# Micron-6.net
KiCad netlist of a schematic drawn in Altium Designer
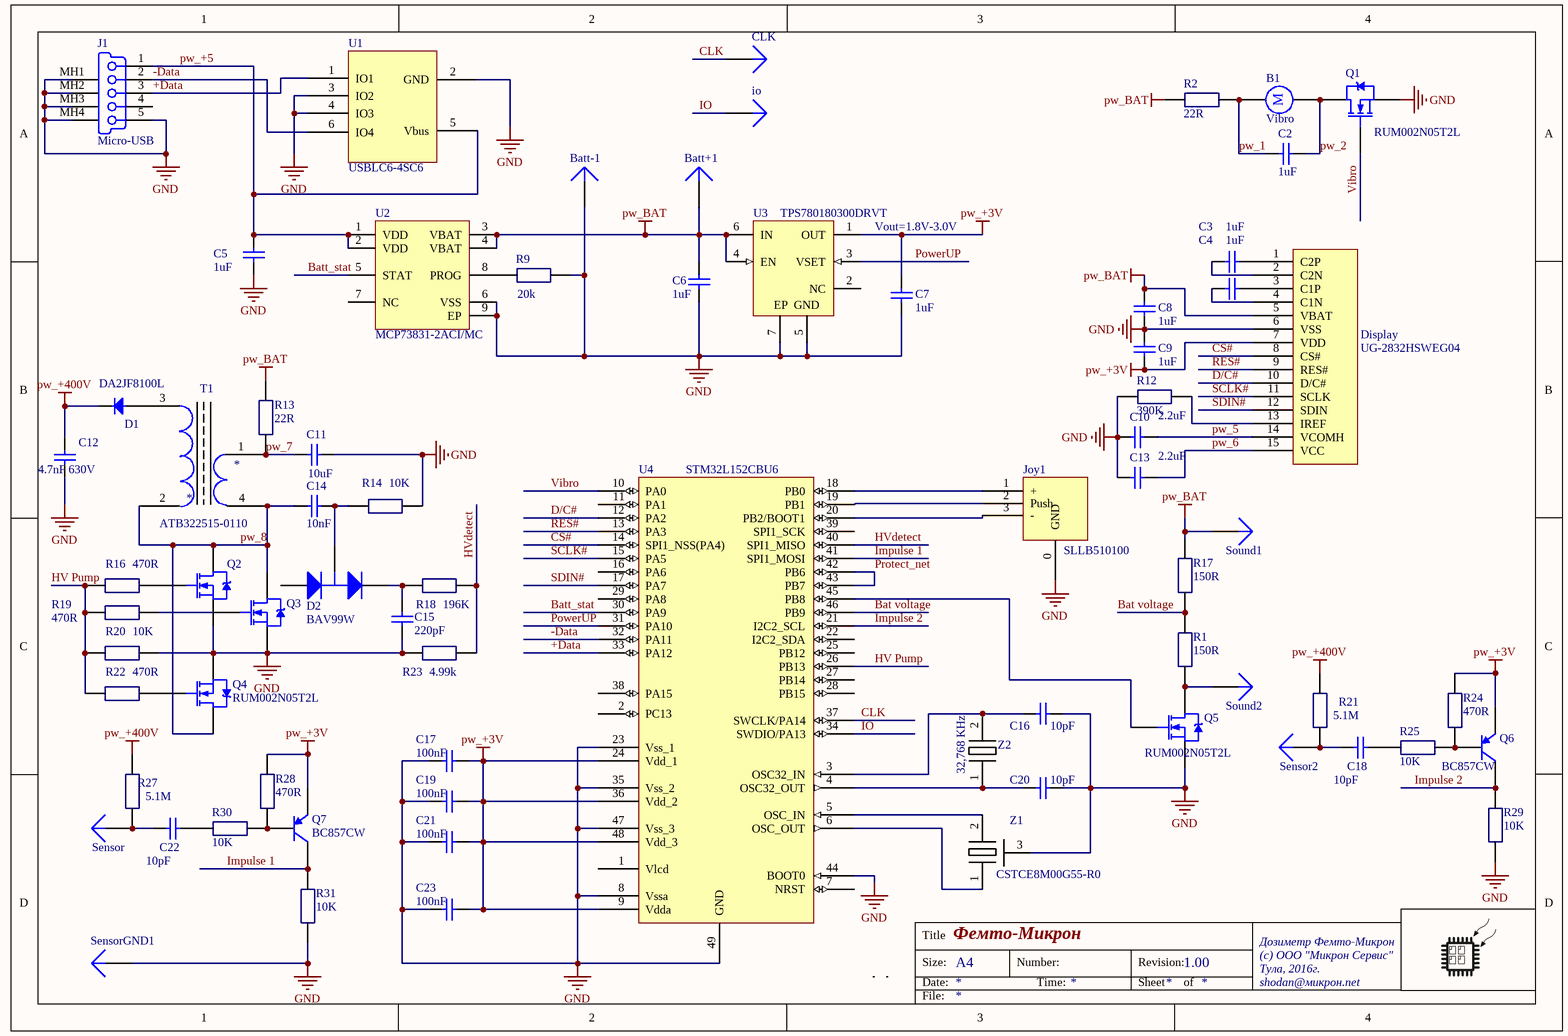
[diagram p0: Micron-6.SchDoc]

(export (version "E")
  (design (tool "Eeschema 10.0.6"))
  (components
    (comp (ref "B1")
      (value "Vibro")
      (footprint "Vibro 4hobby")
      (description "Motor, General Kind")
      (fields (field (name "PUBLISHER") "Altium Limited"))
      (libsource (lib "Miscellaneous Devices") (part "Motor"))
    )
    (comp (ref "Batt+1")
      (value "~")
      (footprint "Sensor contact")
      (description "Plug")
      (fields (field (name "PUBLISHER") "Altium Limited"))
      (libsource (lib "Miscellaneous Connectors") (part "Plug"))
    )
    (comp (ref "Batt-1")
      (value "~")
      (footprint "Sensor contact")
      (description "Plug")
      (fields (field (name "PUBLISHER") "Altium Limited"))
      (libsource (lib "Miscellaneous Connectors") (part "Plug"))
    )
    (comp (ref "C2")
      (value "1uF")
      (footprint "0402 AVX CHK2")
      (description "Capacitor (Semiconductor SIM Model)")
      (fields (field (name "PUBLISHER") "Altium Limited"))
      (libsource (lib "My SCH library") (part "CAPACITOR"))
    )
    (comp (ref "C3")
      (value "1uF")
      (footprint "0402 AVX CHK2")
      (description "Capacitor (Semiconductor SIM Model)")
      (fields (field (name "PUBLISHER") "Altium Limited"))
      (libsource (lib "My SCH library") (part "CAPACITOR"))
    )
    (comp (ref "C4")
      (value "1uF")
      (footprint "0402 AVX CHK2")
      (description "Capacitor (Semiconductor SIM Model)")
      (fields (field (name "PUBLISHER") "Altium Limited"))
      (libsource (lib "My SCH library") (part "CAPACITOR"))
    )
    (comp (ref "C5")
      (value "1uF")
      (footprint "0402 AVX CHK2")
      (description "Capacitor (Semiconductor SIM Model)")
      (fields (field (name "PUBLISHER") "Altium Limited"))
      (libsource (lib "Miscellaneous Devices") (part "Cap Semi"))
    )
    (comp (ref "C6")
      (value "1uF")
      (footprint "0402 AVX CHK2")
      (description "Capacitor (Semiconductor SIM Model)")
      (fields (field (name "PUBLISHER") "Altium Limited"))
      (libsource (lib "My SCH library") (part "CAPACITOR"))
    )
    (comp (ref "C7")
      (value "1uF")
      (footprint "0402 AVX CHK2")
      (description "Capacitor (Semiconductor SIM Model)")
      (fields (field (name "PUBLISHER") "Altium Limited"))
      (libsource (lib "My SCH library") (part "CAPACITOR"))
    )
    (comp (ref "C8")
      (value "1uF")
      (footprint "0402 AVX CHK2")
      (description "Capacitor (Semiconductor SIM Model)")
      (fields (field (name "PUBLISHER") "Altium Limited"))
      (libsource (lib "My SCH library") (part "CAPACITOR"))
    )
    (comp (ref "C9")
      (value "1uF")
      (footprint "0402 AVX CHK2")
      (description "Capacitor (Semiconductor SIM Model)")
      (fields (field (name "PUBLISHER") "Altium Limited"))
      (libsource (lib "My SCH library") (part "CAPACITOR"))
    )
    (comp (ref "C10")
      (value "2.2uF")
      (footprint "Yegeo 0603")
      (description "Capacitor (Semiconductor SIM Model)")
      (fields (field (name "PUBLISHER") "Altium Limited"))
      (libsource (lib "My SCH library") (part "CAPACITOR"))
    )
    (comp (ref "C11")
      (value "10uF")
      (footprint "1608[0603]")
      (description "Capacitor (Semiconductor SIM Model)")
      (fields (field (name "PUBLISHER") "Altium Limited"))
      (libsource (lib "Miscellaneous Devices") (part "Cap Semi"))
    )
    (comp (ref "C12")
      (value "4.7nF 630V")
      (footprint "Miscellaneous Devices:C1206")
      (description "Capacitor (Semiconductor SIM Model)")
      (fields (field (name "PUBLISHER") "Altium Limited"))
      (libsource (lib "Miscellaneous Devices") (part "Cap Semi"))
    )
    (comp (ref "C13")
      (value "2.2uF")
      (footprint "Yegeo 0603")
      (description "Capacitor (Semiconductor SIM Model)")
      (fields (field (name "PUBLISHER") "Altium Limited"))
      (libsource (lib "My SCH library") (part "CAPACITOR"))
    )
    (comp (ref "C14")
      (value "10nF")
      (footprint "0402 AVX CHK2")
      (description "Capacitor (Semiconductor SIM Model)")
      (libsource (lib "Miscellaneous Devices") (part "Cap Semi"))
    )
    (comp (ref "C15")
      (value "220pF")
      (footprint "0402 AVX CHK2")
      (description "Capacitor (Semiconductor SIM Model)")
      (libsource (lib "Miscellaneous Devices") (part "Cap Semi"))
    )
    (comp (ref "C16")
      (value "10pF")
      (footprint "0402 AVX CHK2")
      (description "Capacitor (Semiconductor SIM Model)")
      (fields (field (name "PUBLISHER") "Altium Limited"))
      (libsource (lib "Miscellaneous Devices") (part "Cap Semi"))
    )
    (comp (ref "C17")
      (value "100nF")
      (footprint "0402 AVX CHK2")
      (description "Capacitor (Semiconductor SIM Model)")
      (fields (field (name "PUBLISHER") "Altium Limited"))
      (libsource (lib "Miscellaneous Devices") (part "Cap Semi"))
    )
    (comp (ref "C18")
      (value "10pF")
      (footprint "CC1206JRNPOBBN100")
      (description "Capacitor (Semiconductor SIM Model)")
      (fields (field (name "PUBLISHER") "Altium Limited"))
      (libsource (lib "Miscellaneous Devices") (part "Cap Semi"))
    )
    (comp (ref "C19")
      (value "100nF")
      (footprint "0402 AVX CHK2")
      (description "Capacitor (Semiconductor SIM Model)")
      (fields (field (name "PUBLISHER") "Altium Limited"))
      (libsource (lib "Miscellaneous Devices") (part "Cap Semi"))
    )
    (comp (ref "C20")
      (value "10pF")
      (footprint "0402 AVX CHK2")
      (description "Capacitor (Semiconductor SIM Model)")
      (fields (field (name "PUBLISHER") "Altium Limited"))
      (libsource (lib "Miscellaneous Devices") (part "Cap Semi"))
    )
    (comp (ref "C21")
      (value "100nF")
      (footprint "0402 AVX CHK2")
      (description "Capacitor (Semiconductor SIM Model)")
      (fields (field (name "PUBLISHER") "Altium Limited"))
      (libsource (lib "Miscellaneous Devices") (part "Cap Semi"))
    )
    (comp (ref "C22")
      (value "10pF")
      (footprint "CC1206JRNPOBBN100")
      (description "Capacitor (Semiconductor SIM Model)")
      (fields (field (name "PUBLISHER") "Altium Limited"))
      (libsource (lib "Miscellaneous Devices") (part "Cap Semi"))
    )
    (comp (ref "C23")
      (value "100nF")
      (footprint "0402 AVX CHK2")
      (description "Capacitor (Semiconductor SIM Model)")
      (fields (field (name "PUBLISHER") "Altium Limited"))
      (libsource (lib "Miscellaneous Devices") (part "Cap Semi"))
    )
    (comp (ref "CLK")
      (value "~")
      (footprint "Sensor contact")
      (description "Plug")
      (fields (field (name "PUBLISHER") "Altium Limited"))
      (libsource (lib "Miscellaneous Connectors") (part "Plug"))
    )
    (comp (ref "D1")
      (value "DA2JF8100L")
      (footprint "DA2JF8100L(chk)")
      (description "Diode")
      (libsource (lib "Diodes") (part "Diode"))
    )
    (comp (ref "D2")
      (value "BAV99W")
      (footprint "BAV99W")
      (description "Silicon Switching Diode Array for High-Speed Switching")
      (fields (field (name "PUBLISHER") "Altium Limited"))
      (libsource (lib "Infineon Discrete Diode") (part "BAV99"))
    )
    (comp (ref "Display")
      (value "UG-2832HSWEG04")
      (footprint "UG-2832HSWEG04 - duplicate")
      (libsource (lib "My SCH library") (part "UG-2832HSWEG04"))
    )
    (comp (ref "io")
      (value "~")
      (footprint "Sensor contact")
      (description "Plug")
      (fields (field (name "PUBLISHER") "Altium Limited"))
      (libsource (lib "Miscellaneous Connectors") (part "Plug"))
    )
    (comp (ref "J1")
      (value "Micro-USB")
      (footprint "10118193-0001LF")
      (libsource (lib "Molex Serial Bus Mini USB") (part "0481900001"))
    )
    (comp (ref "Joy1")
      (value "SLLB510100")
      (footprint "SLLB510100")
      (libsource (lib "My SCH library") (part "Joystik"))
    )
    (comp (ref "Q1")
      (value "RUM002N05T2L")
      (footprint "RUM002N05")
      (description "HEXFET Power MOSFET")
      (fields (field (name "PUBLISHER") "Altium Limited"))
      (libsource (lib "IR Discrete MOSFET - Power") (part "IRLML2402"))
    )
    (comp (ref "Q2")
      (value "RUM002N05T2L")
      (footprint "RUM002N05")
      (description "HEXFET Power MOSFET")
      (fields (field (name "PUBLISHER") "Altium Limited"))
      (libsource (lib "IR Discrete MOSFET - Power") (part "IRLML2402"))
    )
    (comp (ref "Q3")
      (value "RUM002N05T2L")
      (footprint "RUM002N05")
      (description "HEXFET Power MOSFET")
      (fields (field (name "PUBLISHER") "Altium Limited"))
      (libsource (lib "IR Discrete MOSFET - Power") (part "IRLML2402"))
    )
    (comp (ref "Q4")
      (value "RUM002N05T2L")
      (footprint "RUM002N05")
      (description "HEXFET Power MOSFET")
      (fields (field (name "PUBLISHER") "Altium Limited"))
      (libsource (lib "IR Discrete MOSFET - Power") (part "IRLML2402"))
    )
    (comp (ref "Q5")
      (value "RUM002N05T2L")
      (footprint "RUM002N05")
      (description "HEXFET Power MOSFET")
      (fields (field (name "PUBLISHER") "Altium Limited"))
      (libsource (lib "IR Discrete MOSFET - Power") (part "IRLML2402"))
    )
    (comp (ref "Q6")
      (value "BC857CW")
      (footprint "SOT323_L2")
      (description "PNP General-purpose Transistor")
      (fields (field (name "PUBLISHER") "Altium Limited"))
      (libsource (lib "Philips Discrete BJT - Low Power") (part "BC857CW"))
    )
    (comp (ref "Q7")
      (value "BC857CW")
      (footprint "SOT323_L2")
      (description "PNP General-purpose Transistor")
      (fields (field (name "PUBLISHER") "Altium Limited"))
      (libsource (lib "Philips Discrete BJT - Low Power") (part "BC857CW"))
    )
    (comp (ref "R1")
      (value "150R")
      (footprint "0402 Yageo")
      (libsource (lib "My SCH library") (part "Resistor 0805"))
    )
    (comp (ref "R2")
      (value "22R")
      (footprint "0402 Yageo")
      (libsource (lib "Микрон-3") (part "Resistor 0805"))
    )
    (comp (ref "R9")
      (value "20k")
      (footprint "0402 Yageo")
      (libsource (lib "Микрон-3") (part "Resistor 0805"))
    )
    (comp (ref "R12")
      (value "390K")
      (footprint "0402 Yageo")
      (libsource (lib "My SCH library") (part "Resistor 0805"))
    )
    (comp (ref "R13")
      (value "22R")
      (footprint "0402 Yageo")
      (libsource (lib "Микрон-3") (part "Resistor 0805"))
    )
    (comp (ref "R14")
      (value "10K")
      (footprint "0402 Yageo")
      (libsource (lib "Микрон-3") (part "Resistor 0805"))
    )
    (comp (ref "R16")
      (value "470R")
      (footprint "0402 Yageo")
      (libsource (lib "Микрон-3") (part "Resistor 0805"))
    )
    (comp (ref "R17")
      (value "150R")
      (footprint "0402 Yageo")
      (libsource (lib "My SCH library") (part "Resistor 0805"))
    )
    (comp (ref "R18")
      (value "196K")
      (footprint "0402 Yageo")
      (libsource (lib "My SCH library") (part "Resistor 0805"))
    )
    (comp (ref "R19")
      (value "470R")
      (footprint "0402 Yageo")
      (libsource (lib "Микрон-3") (part "Resistor 0805"))
    )
    (comp (ref "R20")
      (value "10K")
      (footprint "0402 Yageo")
      (libsource (lib "Микрон-3") (part "Resistor 0805"))
    )
    (comp (ref "R21")
      (value "5.1M")
      (footprint "Vishay RCV0805")
      (libsource (lib "Микрон-3") (part "Resistor 0805"))
    )
    (comp (ref "R22")
      (value "470R")
      (footprint "0402 Yageo")
      (libsource (lib "Микрон-3") (part "Resistor 0805"))
    )
    (comp (ref "R23")
      (value "4.99k")
      (footprint "0402 Yageo")
      (libsource (lib "Микрон-3") (part "Resistor 0805"))
    )
    (comp (ref "R24")
      (value "470R")
      (footprint "0402 Yageo")
      (libsource (lib "Микрон-3") (part "Resistor 0805"))
    )
    (comp (ref "R25")
      (value "10K")
      (footprint "0402 Yageo")
      (libsource (lib "Микрон-3") (part "Resistor 0805"))
    )
    (comp (ref "R27")
      (value "5.1M")
      (footprint "Vishay RCV0805")
      (libsource (lib "Микрон-3") (part "Resistor 0805"))
    )
    (comp (ref "R28")
      (value "470R")
      (footprint "0402 Yageo")
      (libsource (lib "Микрон-3") (part "Resistor 0805"))
    )
    (comp (ref "R29")
      (value "10K")
      (footprint "0402 Yageo")
      (libsource (lib "Микрон-3") (part "Resistor 0805"))
    )
    (comp (ref "R30")
      (value "10K")
      (footprint "0402 Yageo")
      (libsource (lib "Микрон-3") (part "Resistor 0805"))
    )
    (comp (ref "R31")
      (value "10K")
      (footprint "0402 Yageo")
      (libsource (lib "Микрон-3") (part "Resistor 0805"))
    )
    (comp (ref "RP1") (value "PR") (footprint "RP - minimum") (libsource (lib "My SCH library") (part "PR")))
    (comp (ref "RP2") (value "PR") (footprint "RP - minimum") (libsource (lib "My SCH library") (part "PR")))
    (comp (ref "Sensor")
      (value "~")
      (footprint "Sensor contact")
      (description "Plug")
      (fields (field (name "PUBLISHER") "Altium Limited"))
      (libsource (lib "Miscellaneous Connectors") (part "Plug"))
    )
    (comp (ref "Sensor2")
      (value "~")
      (footprint "Sensor contact")
      (description "Plug")
      (fields (field (name "PUBLISHER") "Altium Limited"))
      (libsource (lib "Miscellaneous Connectors") (part "Plug"))
    )
    (comp (ref "SensorGND1")
      (value "~")
      (footprint "Sensor contact")
      (description "Plug")
      (fields (field (name "PUBLISHER") "Altium Limited"))
      (libsource (lib "Miscellaneous Connectors") (part "Plug"))
    )
    (comp (ref "Sound1")
      (value "~")
      (footprint "Sensor contact")
      (description "Plug")
      (fields (field (name "PUBLISHER") "Altium Limited"))
      (libsource (lib "Miscellaneous Connectors") (part "Plug"))
    )
    (comp (ref "Sound2")
      (value "~")
      (footprint "Sensor contact")
      (description "Plug")
      (fields (field (name "PUBLISHER") "Altium Limited"))
      (libsource (lib "Miscellaneous Connectors") (part "Plug"))
    )
    (comp (ref "T1")
      (value "ATB322515-0110")
      (footprint "ATB322515-0110")
      (libsource (lib "My SCH library") (part "ATB322515-0110"))
    )
    (comp (ref "U1")
      (value "USBLC6-4SC6")
      (footprint "USBLC6-4")
      (libsource (lib "My SCH library") (part "USBLC6-4SC6"))
    )
    (comp (ref "U2")
      (value "MCP73831-2ACI/MC")
      (footprint "DFN-MC8")
      (description "=Order")
      (fields (field (name "PUBLISHER") "Altium Limited"))
      (libsource (lib "Microchip Power Mgt Battery Management") (part "MCP73832T-2ACI/MC"))
    )
    (comp (ref "U3")
      (value "TPS780180300DRVT")
      (footprint "TI-DRV6-1600X1000TP_V")
      (fields (field (name "MANUFACTURER") "Texas Instruments"))
      (libsource (lib "TI Power Management Linear Regulator Single Channel LDO (0-350mA)") (part "TPS780180300DRVT"))
    )
    (comp (ref "U4")
      (value "STM32L152CBU6")
      (footprint "STM32L152CBU6-small")
      (libsource (lib "Micron-3.2") (part "STM32L152CBU6"))
    )
    (comp (ref "Z1")
      (value "CSTCE8M00G55-R0")
      (footprint "CSTCE_G15C")
      (libsource (lib "My SCH library") (part "8MHZ_cap"))
    )
    (comp (ref "Z2")
      (value "32,768 KHz")
      (footprint "ABS07-120-32.768kHz-T")
      (libsource (lib "Микрон-3") (part "8MHZ"))
    )
  )
  (nets
    (net (code "1") (name "/+Data") (class "Default")
      (node (ref "J1") (pin "3") (pinfunction "D+_3") (pintype "passive"))
      (node (ref "U1") (pin "1") (pinfunction "IO1_1") (pintype "passive"))
      (node (ref "U4") (pin "33") (pinfunction "PA12_33") (pintype "bidirectional"))
    )
    (net (code "2") (name "/-Data") (class "Default")
      (node (ref "J1") (pin "2") (pinfunction "D-_2") (pintype "passive"))
      (node (ref "U1") (pin "6") (pinfunction "IO4_6") (pintype "passive"))
      (node (ref "U4") (pin "32") (pinfunction "PA11_32") (pintype "bidirectional"))
    )
    (net (code "3") (name "/Bat voltage") (class "Default")
      (node (ref "R1") (pin "1") (pinfunction "A_1") (pintype "passive"))
      (node (ref "R17") (pin "2") (pinfunction "2_2") (pintype "passive"))
      (node (ref "U4") (pin "46") (pinfunction "PB9_46") (pintype "bidirectional"))
    )
    (net (code "4") (name "/Batt_stat") (class "Default")
      (node (ref "U2") (pin "5") (pinfunction "STAT_5") (pintype "open_collector"))
      (node (ref "U4") (pin "30") (pinfunction "PA9_30") (pintype "bidirectional"))
    )
    (net (code "5") (name "/CLK") (class "Default")
      (node (ref "CLK") (pin "1") (pinfunction "1_1") (pintype "passive"))
      (node (ref "U4") (pin "37") (pinfunction "SWCLK/PA14_37") (pintype "bidirectional"))
    )
    (net (code "6") (name "/CS#") (class "Default")
      (node (ref "Display") (pin "8") (pinfunction "CS#_8") (pintype "open_collector"))
      (node (ref "U4") (pin "14") (pinfunction "SPI1_NSS(PA4)_14") (pintype "bidirectional"))
    )
    (net (code "7") (name "/D{slash}C#") (class "Default")
      (node (ref "Display") (pin "10") (pinfunction "D/C#_10") (pintype "open_collector"))
      (node (ref "U4") (pin "12") (pinfunction "PA2_12") (pintype "bidirectional"))
    )
    (net (code "8") (name "/HV Pump") (class "Default")
      (node (ref "R16") (pin "2") (pinfunction "2_2") (pintype "passive"))
      (node (ref "R19") (pin "2") (pinfunction "2_2") (pintype "passive"))
      (node (ref "R20") (pin "2") (pinfunction "2_2") (pintype "passive"))
      (node (ref "R22") (pin "2") (pinfunction "2_2") (pintype "passive"))
      (node (ref "U4") (pin "26") (pinfunction "PB13_26") (pintype "bidirectional"))
    )
    (net (code "9") (name "/HVdetect") (class "Default")
      (node (ref "R18") (pin "2") (pinfunction "2_2") (pintype "passive"))
      (node (ref "R23") (pin "1") (pinfunction "A_1") (pintype "passive"))
      (node (ref "U4") (pin "40") (pinfunction "SPI1_MISO_40") (pintype "bidirectional"))
    )
    (net (code "10") (name "/IO") (class "Default")
      (node (ref "U4") (pin "34") (pinfunction "SWDIO/PA13_34") (pintype "bidirectional"))
      (node (ref "io") (pin "1") (pinfunction "1_1") (pintype "passive"))
    )
    (net (code "11") (name "/Impulse 1") (class "Default")
      (node (ref "Q7") (pin "3") (pinfunction "C_3") (pintype "passive"))
      (node (ref "R31") (pin "1") (pinfunction "A_1") (pintype "passive"))
      (node (ref "U4") (pin "41") (pinfunction "SPI1_MOSI_41") (pintype "bidirectional"))
    )
    (net (code "12") (name "/Impulse 2") (class "Default")
      (node (ref "Q6") (pin "3") (pinfunction "C_3") (pintype "passive"))
      (node (ref "R29") (pin "1") (pinfunction "A_1") (pintype "passive"))
      (node (ref "U4") (pin "21") (pinfunction "I2C2_SCL_21") (pintype "bidirectional"))
    )
    (net (code "13") (name "/PowerUP") (class "Default")
      (node (ref "U3") (pin "3") (pinfunction "VSET_3") (pintype "input"))
      (node (ref "U4") (pin "31") (pinfunction "PA10_31") (pintype "bidirectional"))
    )
    (net (code "14") (name "/Protect_net") (class "Default")
      (node (ref "U4") (pin "42") (pinfunction "PB6_42") (pintype "bidirectional"))
      (node (ref "U4") (pin "43") (pinfunction "PB7_43") (pintype "bidirectional"))
    )
    (net (code "15") (name "/RES#") (class "Default")
      (node (ref "Display") (pin "9") (pinfunction "RES#_9") (pintype "open_collector"))
      (node (ref "U4") (pin "13") (pinfunction "PA3_13") (pintype "bidirectional"))
    )
    (net (code "16") (name "/SCLK#") (class "Default")
      (node (ref "Display") (pin "11") (pinfunction "SCLK_11") (pintype "open_collector"))
      (node (ref "U4") (pin "15") (pinfunction "PA5_15") (pintype "bidirectional"))
    )
    (net (code "17") (name "/SDIN#") (class "Default")
      (node (ref "Display") (pin "12") (pinfunction "SDIN_12") (pintype "open_collector"))
      (node (ref "U4") (pin "17") (pinfunction "PA7_17") (pintype "bidirectional"))
    )
    (net (code "18") (name "/Vibro") (class "Default")
      (node (ref "Q1") (pin "1") (pinfunction "G_1") (pintype "passive"))
      (node (ref "U4") (pin "10") (pinfunction "PA0_10") (pintype "bidirectional"))
    )
    (net (code "19") (name "/pw_+5") (class "Default")
      (node (ref "C5") (pin "2") (pinfunction "2_2") (pintype "passive"))
      (node (ref "J1") (pin "1") (pinfunction "V_BUS_(5V)_1") (pintype "passive"))
      (node (ref "U1") (pin "5") (pinfunction "Vbus_5") (pintype "passive"))
      (node (ref "U2") (pin "1") (pinfunction "VDD_1") (pintype "power_in"))
      (node (ref "U2") (pin "2") (pinfunction "VDD_2") (pintype "power_in"))
    )
    (net (code "20") (name "/pw_1") (class "Default")
      (node (ref "B1") (pin "1") (pinfunction "1_1") (pintype "passive"))
      (node (ref "C2") (pin "2") (pinfunction "2_2") (pintype "passive"))
      (node (ref "R2") (pin "2") (pinfunction "2_2") (pintype "passive"))
    )
    (net (code "21") (name "/pw_2") (class "Default")
      (node (ref "B1") (pin "2") (pinfunction "2_2") (pintype "passive"))
      (node (ref "C2") (pin "1") (pinfunction "1_1") (pintype "passive"))
      (node (ref "Q1") (pin "3") (pinfunction "D_3") (pintype "passive"))
    )
    (net (code "22") (name "/pw_5") (class "Default")
      (node (ref "C10") (pin "1") (pinfunction "1_1") (pintype "passive"))
      (node (ref "Display") (pin "14") (pinfunction "VCOMH_14") (pintype "open_collector"))
    )
    (net (code "23") (name "/pw_6") (class "Default")
      (node (ref "C13") (pin "1") (pinfunction "1_1") (pintype "passive"))
      (node (ref "Display") (pin "15") (pinfunction "VCC_15") (pintype "open_collector"))
    )
    (net (code "24") (name "/pw_7") (class "Default")
      (node (ref "C11") (pin "2") (pinfunction "2_2") (pintype "passive"))
      (node (ref "R13") (pin "2") (pinfunction "2_2") (pintype "passive"))
      (node (ref "T1") (pin "1") (pinfunction "1_1") (pintype "passive"))
    )
    (net (code "25") (name "/pw_8") (class "Default")
      (node (ref "C14") (pin "1") (pinfunction "1_1") (pintype "passive"))
      (node (ref "Q2") (pin "3") (pinfunction "D_3") (pintype "passive"))
      (node (ref "Q3") (pin "3") (pinfunction "D_3") (pintype "passive"))
      (node (ref "Q4") (pin "3") (pinfunction "D_3") (pintype "passive"))
      (node (ref "T1") (pin "2") (pinfunction "2_2") (pintype "passive"))
      (node (ref "T1") (pin "4") (pintype "passive"))
    )
    (net (code "26") (name "GND") (class "Default")
      (node (ref "Batt-1") (pin "1") (pinfunction "1_1") (pintype "passive"))
      (node (ref "C10") (pin "2") (pinfunction "2_2") (pintype "passive"))
      (node (ref "C11") (pin "1") (pinfunction "1_1") (pintype "passive"))
      (node (ref "C12") (pin "1") (pinfunction "1_1") (pintype "passive"))
      (node (ref "C13") (pin "2") (pinfunction "2_2") (pintype "passive"))
      (node (ref "C15") (pin "2") (pinfunction "2_2") (pintype "passive"))
      (node (ref "C16") (pin "1") (pinfunction "1_1") (pintype "passive"))
      (node (ref "C17") (pin "2") (pinfunction "2_2") (pintype "passive"))
      (node (ref "C19") (pin "2") (pinfunction "2_2") (pintype "passive"))
      (node (ref "C20") (pin "1") (pinfunction "1_1") (pintype "passive"))
      (node (ref "C21") (pin "2") (pinfunction "2_2") (pintype "passive"))
      (node (ref "C23") (pin "2") (pinfunction "2_2") (pintype "passive"))
      (node (ref "C5") (pin "1") (pinfunction "1_1") (pintype "passive"))
      (node (ref "C6") (pin "1") (pinfunction "1_1") (pintype "passive"))
      (node (ref "C7") (pin "1") (pinfunction "1_1") (pintype "passive"))
      (node (ref "C8") (pin "1") (pinfunction "1_1") (pintype "passive"))
      (node (ref "C9") (pin "2") (pinfunction "2_2") (pintype "passive"))
      (node (ref "Display") (pin "6") (pinfunction "VSS_6") (pintype "open_collector"))
      (node (ref "J1") (pin "5") (pinfunction "GND_5") (pintype "passive"))
      (node (ref "J1") (pin "MH1") (pinfunction "Tab_MH1") (pintype "passive"))
      (node (ref "J1") (pin "MH2") (pinfunction "Tab_MH2") (pintype "passive"))
      (node (ref "J1") (pin "MH3") (pinfunction "Tab_MH3") (pintype "passive"))
      (node (ref "J1") (pin "MH4") (pinfunction "Tab_MH4") (pintype "passive"))
      (node (ref "Joy1") (pin "0") (pinfunction "GND_0") (pintype "open_collector"))
      (node (ref "Q1") (pin "2") (pinfunction "S_2") (pintype "passive"))
      (node (ref "Q2") (pin "2") (pinfunction "S_2") (pintype "passive"))
      (node (ref "Q3") (pin "2") (pinfunction "S_2") (pintype "passive"))
      (node (ref "Q4") (pin "2") (pinfunction "S_2") (pintype "passive"))
      (node (ref "Q5") (pin "2") (pinfunction "S_2") (pintype "passive"))
      (node (ref "R12") (pin "1") (pinfunction "A_1") (pintype "passive"))
      (node (ref "R14") (pin "1") (pinfunction "A_1") (pintype "passive"))
      (node (ref "R20") (pin "1") (pinfunction "A_1") (pintype "passive"))
      (node (ref "R23") (pin "2") (pinfunction "2_2") (pintype "passive"))
      (node (ref "R29") (pin "2") (pinfunction "2_2") (pintype "passive"))
      (node (ref "R31") (pin "2") (pinfunction "2_2") (pintype "passive"))
      (node (ref "R9") (pin "1") (pinfunction "A_1") (pintype "passive"))
      (node (ref "SensorGND1") (pin "1") (pinfunction "1_1") (pintype "passive"))
      (node (ref "U1") (pin "2") (pinfunction "GND_2") (pintype "passive"))
      (node (ref "U1") (pin "3") (pinfunction "IO2_3") (pintype "passive"))
      (node (ref "U1") (pin "4") (pinfunction "IO3_4") (pintype "passive"))
      (node (ref "U2") (pin "6") (pinfunction "VSS_6") (pintype "power_in"))
      (node (ref "U2") (pin "9") (pinfunction "EP_9") (pintype "power_in"))
      (node (ref "U3") (pin "5") (pinfunction "GND_5") (pintype "power_in"))
      (node (ref "U3") (pin "7") (pinfunction "EP_7") (pintype "power_in"))
      (node (ref "U4") (pin "23") (pinfunction "Vss_1_23") (pintype "power_in"))
      (node (ref "U4") (pin "35") (pinfunction "Vss_2_35") (pintype "power_in"))
      (node (ref "U4") (pin "44") (pinfunction "BOOT0_44") (pintype "input"))
      (node (ref "U4") (pin "47") (pinfunction "Vss_3_47") (pintype "power_in"))
      (node (ref "U4") (pin "49") (pinfunction "GND_49") (pintype "power_in"))
      (node (ref "U4") (pin "8") (pinfunction "Vssa_8") (pintype "power_in"))
      (node (ref "Z1") (pin "3") (pinfunction "50_3") (pintype "passive"))
    )
    (net (code "27") (name "Net-(D1-A)") (class "Default")
      (node (ref "D1") (pin "2") (pinfunction "A_2") (pintype "passive"))
      (node (ref "T1") (pin "3") (pinfunction "3_3") (pintype "passive"))
    )
    (net (code "28") (name "Net-(D2-C)") (class "Default")
      (node (ref "C14") (pin "2") (pinfunction "2_2") (pintype "passive"))
      (node (ref "D2") (pin "3") (pinfunction "C_3") (pintype "passive"))
      (node (ref "R14") (pin "2") (pinfunction "2_2") (pintype "passive"))
    )
    (net (code "29") (name "Net-(D2-K)") (class "Default")
      (node (ref "C15") (pin "1") (pinfunction "1_1") (pintype "passive"))
      (node (ref "D2") (pin "2") (pinfunction "K_2") (pintype "passive"))
      (node (ref "R18") (pin "1") (pinfunction "A_1") (pintype "passive"))
    )
    (net (code "30") (name "Net-(Display-C1N)") (class "Default")
      (node (ref "C4") (pin "2") (pinfunction "2_2") (pintype "passive"))
      (node (ref "Display") (pin "4") (pinfunction "C1N_4") (pintype "open_collector"))
    )
    (net (code "31") (name "Net-(Display-C1P)") (class "Default")
      (node (ref "C4") (pin "1") (pinfunction "1_1") (pintype "passive"))
      (node (ref "Display") (pin "3") (pinfunction "C1P_3") (pintype "open_collector"))
    )
    (net (code "32") (name "Net-(Display-C2N)") (class "Default")
      (node (ref "C3") (pin "2") (pinfunction "2_2") (pintype "passive"))
      (node (ref "Display") (pin "2") (pinfunction "C2N_2") (pintype "open_collector"))
    )
    (net (code "33") (name "Net-(Display-C2P)") (class "Default")
      (node (ref "C3") (pin "1") (pinfunction "1_1") (pintype "passive"))
      (node (ref "Display") (pin "1") (pinfunction "C2P_1") (pintype "open_collector"))
    )
    (net (code "34") (name "Net-(Display-IREF)") (class "Default")
      (node (ref "Display") (pin "13") (pinfunction "IREF_13") (pintype "open_collector"))
      (node (ref "R12") (pin "2") (pinfunction "2_2") (pintype "passive"))
    )
    (net (code "35") (name "Net-(Joy1-+)") (class "Default")
      (node (ref "Joy1") (pin "1") (pinfunction "+_1") (pintype "open_collector"))
      (node (ref "U4") (pin "18") (pinfunction "PB0_18") (pintype "bidirectional"))
    )
    (net (code "36") (name "Net-(Joy1--)") (class "Default")
      (node (ref "Joy1") (pin "3") (pinfunction "-_3") (pintype "open_collector"))
      (node (ref "U4") (pin "20") (pinfunction "PB2/BOOT1_20") (pintype "bidirectional"))
    )
    (net (code "37") (name "Net-(Joy1-Push)") (class "Default")
      (node (ref "Joy1") (pin "2") (pinfunction "Push_2") (pintype "open_collector"))
      (node (ref "U4") (pin "19") (pinfunction "PB1_19") (pintype "bidirectional"))
    )
    (net (code "38") (name "Net-(Q2-G)") (class "Default")
      (node (ref "Q2") (pin "1") (pinfunction "G_1") (pintype "passive"))
      (node (ref "R16") (pin "1") (pinfunction "A_1") (pintype "passive"))
    )
    (net (code "39") (name "Net-(Q3-G)") (class "Default")
      (node (ref "Q3") (pin "1") (pinfunction "G_1") (pintype "passive"))
      (node (ref "R19") (pin "1") (pinfunction "A_1") (pintype "passive"))
    )
    (net (code "40") (name "Net-(Q4-G)") (class "Default")
      (node (ref "Q4") (pin "1") (pinfunction "G_1") (pintype "passive"))
      (node (ref "R22") (pin "1") (pinfunction "A_1") (pintype "passive"))
    )
    (net (code "41") (name "Net-(Q5-D)") (class "Default")
      (node (ref "Q5") (pin "3") (pinfunction "D_3") (pintype "passive"))
      (node (ref "R1") (pin "2") (pinfunction "2_2") (pintype "passive"))
      (node (ref "Sound2") (pin "1") (pinfunction "1_1") (pintype "passive"))
    )
    (net (code "42") (name "Net-(Q5-G)") (class "Default")
      (node (ref "Q5") (pin "1") (pinfunction "G_1") (pintype "passive"))
      (node (ref "U4") (pin "45") (pinfunction "PB8_45") (pintype "bidirectional"))
    )
    (net (code "43") (name "Net-(Q6-B)") (class "Default")
      (node (ref "Q6") (pin "1") (pinfunction "B_1") (pintype "passive"))
      (node (ref "R24") (pin "2") (pinfunction "2_2") (pintype "passive"))
      (node (ref "R25") (pin "2") (pinfunction "2_2") (pintype "passive"))
    )
    (net (code "44") (name "Net-(Q7-B)") (class "Default")
      (node (ref "Q7") (pin "1") (pinfunction "B_1") (pintype "passive"))
      (node (ref "R28") (pin "2") (pinfunction "2_2") (pintype "passive"))
      (node (ref "R30") (pin "2") (pinfunction "2_2") (pintype "passive"))
    )
    (net (code "45") (name "Net-(R21-A)") (class "Default")
      (node (ref "C18") (pin "2") (pinfunction "2_2") (pintype "passive"))
      (node (ref "R21") (pin "1") (pinfunction "A_1") (pintype "passive"))
      (node (ref "Sensor2") (pin "1") (pinfunction "1_1") (pintype "passive"))
    )
    (net (code "46") (name "Net-(R25-A)") (class "Default")
      (node (ref "C18") (pin "1") (pinfunction "1_1") (pintype "passive"))
      (node (ref "R25") (pin "1") (pinfunction "A_1") (pintype "passive"))
    )
    (net (code "47") (name "Net-(R27-A)") (class "Default")
      (node (ref "C22") (pin "2") (pinfunction "2_2") (pintype "passive"))
      (node (ref "R27") (pin "1") (pinfunction "A_1") (pintype "passive"))
      (node (ref "Sensor") (pin "1") (pinfunction "1_1") (pintype "passive"))
    )
    (net (code "48") (name "Net-(R30-A)") (class "Default")
      (node (ref "C22") (pin "1") (pinfunction "1_1") (pintype "passive"))
      (node (ref "R30") (pin "1") (pinfunction "A_1") (pintype "passive"))
    )
    (net (code "49") (name "Net-(U2-PROG)") (class "Default")
      (node (ref "R9") (pin "2") (pinfunction "2_2") (pintype "passive"))
      (node (ref "U2") (pin "8") (pinfunction "PROG_8") (pintype "passive"))
    )
    (net (code "50") (name "Net-(U4-OSC32_IN)") (class "Default")
      (node (ref "C16") (pin "2") (pinfunction "2_2") (pintype "passive"))
      (node (ref "U4") (pin "3") (pinfunction "OSC32_IN_3") (pintype "input"))
      (node (ref "Z2") (pin "2") (pinfunction "2_2") (pintype "passive"))
    )
    (net (code "51") (name "Net-(U4-OSC32_OUT)") (class "Default")
      (node (ref "C20") (pin "2") (pinfunction "2_2") (pintype "passive"))
      (node (ref "U4") (pin "4") (pinfunction "OSC32_OUT_4") (pintype "output"))
      (node (ref "Z2") (pin "1") (pinfunction "50_1") (pintype "passive"))
    )
    (net (code "52") (name "Net-(U4-OSC_IN)") (class "Default")
      (node (ref "U4") (pin "5") (pinfunction "OSC_IN_5") (pintype "input"))
      (node (ref "Z1") (pin "2") (pinfunction "2_2") (pintype "passive"))
    )
    (net (code "53") (name "Net-(U4-OSC_OUT)") (class "Default")
      (node (ref "U4") (pin "6") (pinfunction "OSC_OUT_6") (pintype "output"))
      (node (ref "Z1") (pin "1") (pinfunction "50_1") (pintype "passive"))
    )
    (net (code "54") (name "pw_+3V") (class "Default")
      (node (ref "C17") (pin "1") (pinfunction "1_1") (pintype "passive"))
      (node (ref "C19") (pin "1") (pinfunction "1_1") (pintype "passive"))
      (node (ref "C21") (pin "1") (pinfunction "1_1") (pintype "passive"))
      (node (ref "C23") (pin "1") (pinfunction "1_1") (pintype "passive"))
      (node (ref "C7") (pin "2") (pinfunction "2_2") (pintype "passive"))
      (node (ref "C9") (pin "1") (pinfunction "1_1") (pintype "passive"))
      (node (ref "Display") (pin "7") (pinfunction "VDD_7") (pintype "open_collector"))
      (node (ref "Q6") (pin "2") (pinfunction "E_2") (pintype "passive"))
      (node (ref "Q7") (pin "2") (pinfunction "E_2") (pintype "passive"))
      (node (ref "R24") (pin "1") (pinfunction "A_1") (pintype "passive"))
      (node (ref "R28") (pin "1") (pinfunction "A_1") (pintype "passive"))
      (node (ref "U3") (pin "1") (pinfunction "OUT_1") (pintype "power_in"))
      (node (ref "U4") (pin "24") (pinfunction "Vdd_1_24") (pintype "power_in"))
      (node (ref "U4") (pin "36") (pinfunction "Vdd_2_36") (pintype "power_in"))
      (node (ref "U4") (pin "48") (pinfunction "Vdd_3_48") (pintype "power_in"))
      (node (ref "U4") (pin "9") (pinfunction "Vdda_9") (pintype "power_in"))
    )
    (net (code "55") (name "pw_+400V") (class "Default")
      (node (ref "C12") (pin "2") (pinfunction "2_2") (pintype "passive"))
      (node (ref "D1") (pin "1") (pinfunction "C_1") (pintype "passive"))
      (node (ref "R21") (pin "2") (pinfunction "2_2") (pintype "passive"))
      (node (ref "R27") (pin "2") (pinfunction "2_2") (pintype "passive"))
    )
    (net (code "56") (name "pw_BAT") (class "Default")
      (node (ref "Batt+1") (pin "1") (pinfunction "1_1") (pintype "passive"))
      (node (ref "C6") (pin "2") (pinfunction "2_2") (pintype "passive"))
      (node (ref "C8") (pin "2") (pinfunction "2_2") (pintype "passive"))
      (node (ref "Display") (pin "5") (pinfunction "VBAT_5") (pintype "open_collector"))
      (node (ref "R13") (pin "1") (pinfunction "A_1") (pintype "passive"))
      (node (ref "R17") (pin "1") (pinfunction "A_1") (pintype "passive"))
      (node (ref "R2") (pin "1") (pinfunction "A_1") (pintype "passive"))
      (node (ref "Sound1") (pin "1") (pinfunction "1_1") (pintype "passive"))
      (node (ref "U2") (pin "3") (pinfunction "VBAT_3") (pintype "power_in"))
      (node (ref "U2") (pin "4") (pinfunction "VBAT_4") (pintype "power_in"))
      (node (ref "U3") (pin "4") (pinfunction "EN_4") (pintype "input"))
      (node (ref "U3") (pin "6") (pinfunction "IN_6") (pintype "power_in"))
    )
    (net (code "57") (name "unconnected-(D2-A-Pad1)") (class "Default")
      (node (ref "D2") (pin "1") (pinfunction "A_1") (pintype "passive"))
    )
    (net (code "58") (name "unconnected-(J1-NC-Pad4)") (class "Default")
      (node (ref "J1") (pin "4") (pinfunction "NC_4") (pintype "passive"))
    )
    (net (code "59") (name "unconnected-(RP1-Pad0)") (class "Default")
      (node (ref "RP1") (pin "0") (pinfunction "0_0") (pintype "passive"))
    )
    (net (code "60") (name "unconnected-(RP2-Pad0)") (class "Default")
      (node (ref "RP2") (pin "0") (pinfunction "0_0") (pintype "passive"))
    )
    (net (code "61") (name "unconnected-(U2-NC-Pad7)") (class "Default")
      (node (ref "U2") (pin "7") (pinfunction "NC_7") (pintype "passive"))
    )
    (net (code "62") (name "unconnected-(U3-NC-Pad2)") (class "Default")
      (node (ref "U3") (pin "2") (pinfunction "NC_2") (pintype "passive"))
    )
    (net (code "63") (name "unconnected-(U4-I2C2_SDA-Pad22)") (class "Default")
      (node (ref "U4") (pin "22") (pinfunction "I2C2_SDA_22") (pintype "bidirectional"))
    )
    (net (code "64") (name "unconnected-(U4-NRST-Pad7)") (class "Default")
      (node (ref "U4") (pin "7") (pinfunction "NRST_7") (pintype "bidirectional"))
    )
    (net (code "65") (name "unconnected-(U4-PA1-Pad11)") (class "Default")
      (node (ref "U4") (pin "11") (pinfunction "PA1_11") (pintype "bidirectional"))
    )
    (net (code "66") (name "unconnected-(U4-PA6-Pad16)") (class "Default")
      (node (ref "U4") (pin "16") (pinfunction "PA6_16") (pintype "bidirectional"))
    )
    (net (code "67") (name "unconnected-(U4-PA8-Pad29)") (class "Default")
      (node (ref "U4") (pin "29") (pinfunction "PA8_29") (pintype "bidirectional"))
    )
    (net (code "68") (name "unconnected-(U4-PA15-Pad38)") (class "Default")
      (node (ref "U4") (pin "38") (pinfunction "PA15_38") (pintype "bidirectional"))
    )
    (net (code "69") (name "unconnected-(U4-PB12-Pad25)") (class "Default")
      (node (ref "U4") (pin "25") (pinfunction "PB12_25") (pintype "bidirectional"))
    )
    (net (code "70") (name "unconnected-(U4-PB14-Pad27)") (class "Default")
      (node (ref "U4") (pin "27") (pinfunction "PB14_27") (pintype "bidirectional"))
    )
    (net (code "71") (name "unconnected-(U4-PB15-Pad28)") (class "Default")
      (node (ref "U4") (pin "28") (pinfunction "PB15_28") (pintype "bidirectional"))
    )
    (net (code "72") (name "unconnected-(U4-PC13-Pad2)") (class "Default")
      (node (ref "U4") (pin "2") (pinfunction "PC13_2") (pintype "bidirectional"))
    )
    (net (code "73") (name "unconnected-(U4-SPI1_SCK-Pad39)") (class "Default")
      (node (ref "U4") (pin "39") (pinfunction "SPI1_SCK_39") (pintype "bidirectional"))
    )
    (net (code "74") (name "unconnected-(U4-Vlcd-Pad1)") (class "Default")
      (node (ref "U4") (pin "1") (pinfunction "Vlcd_1") (pintype "power_in"))
    )
  )
)
